# airball_sensor_board_v6.net
KiCad netlist of a schematic drawn in EAGLE
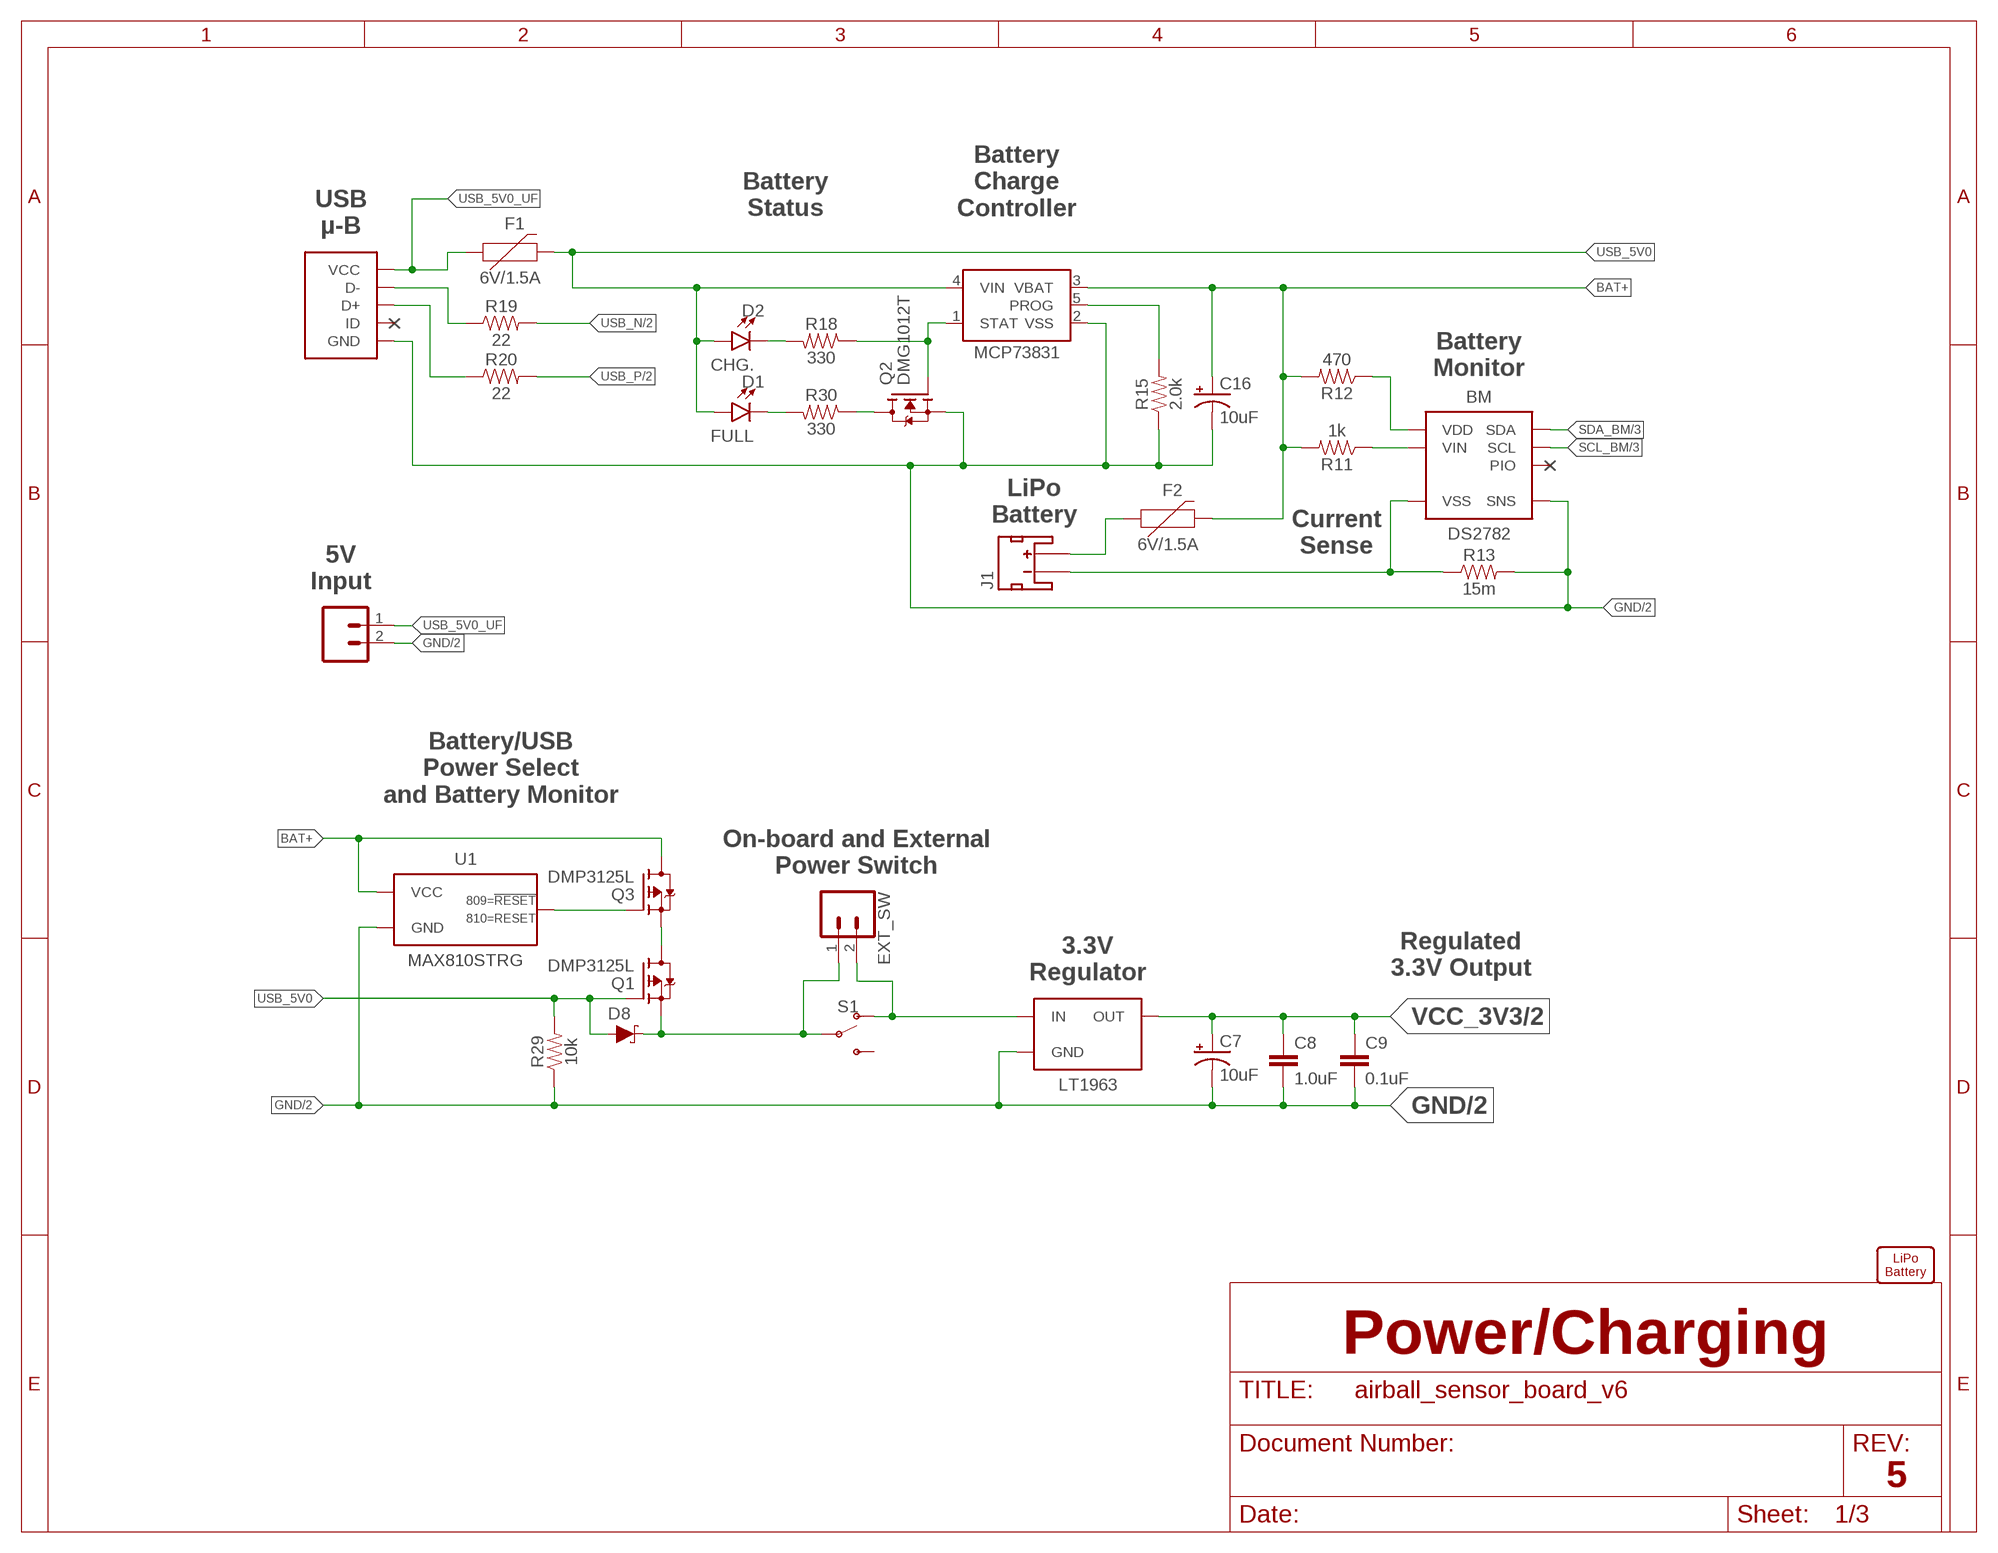
[diagram p0: schematic, sheet 1]
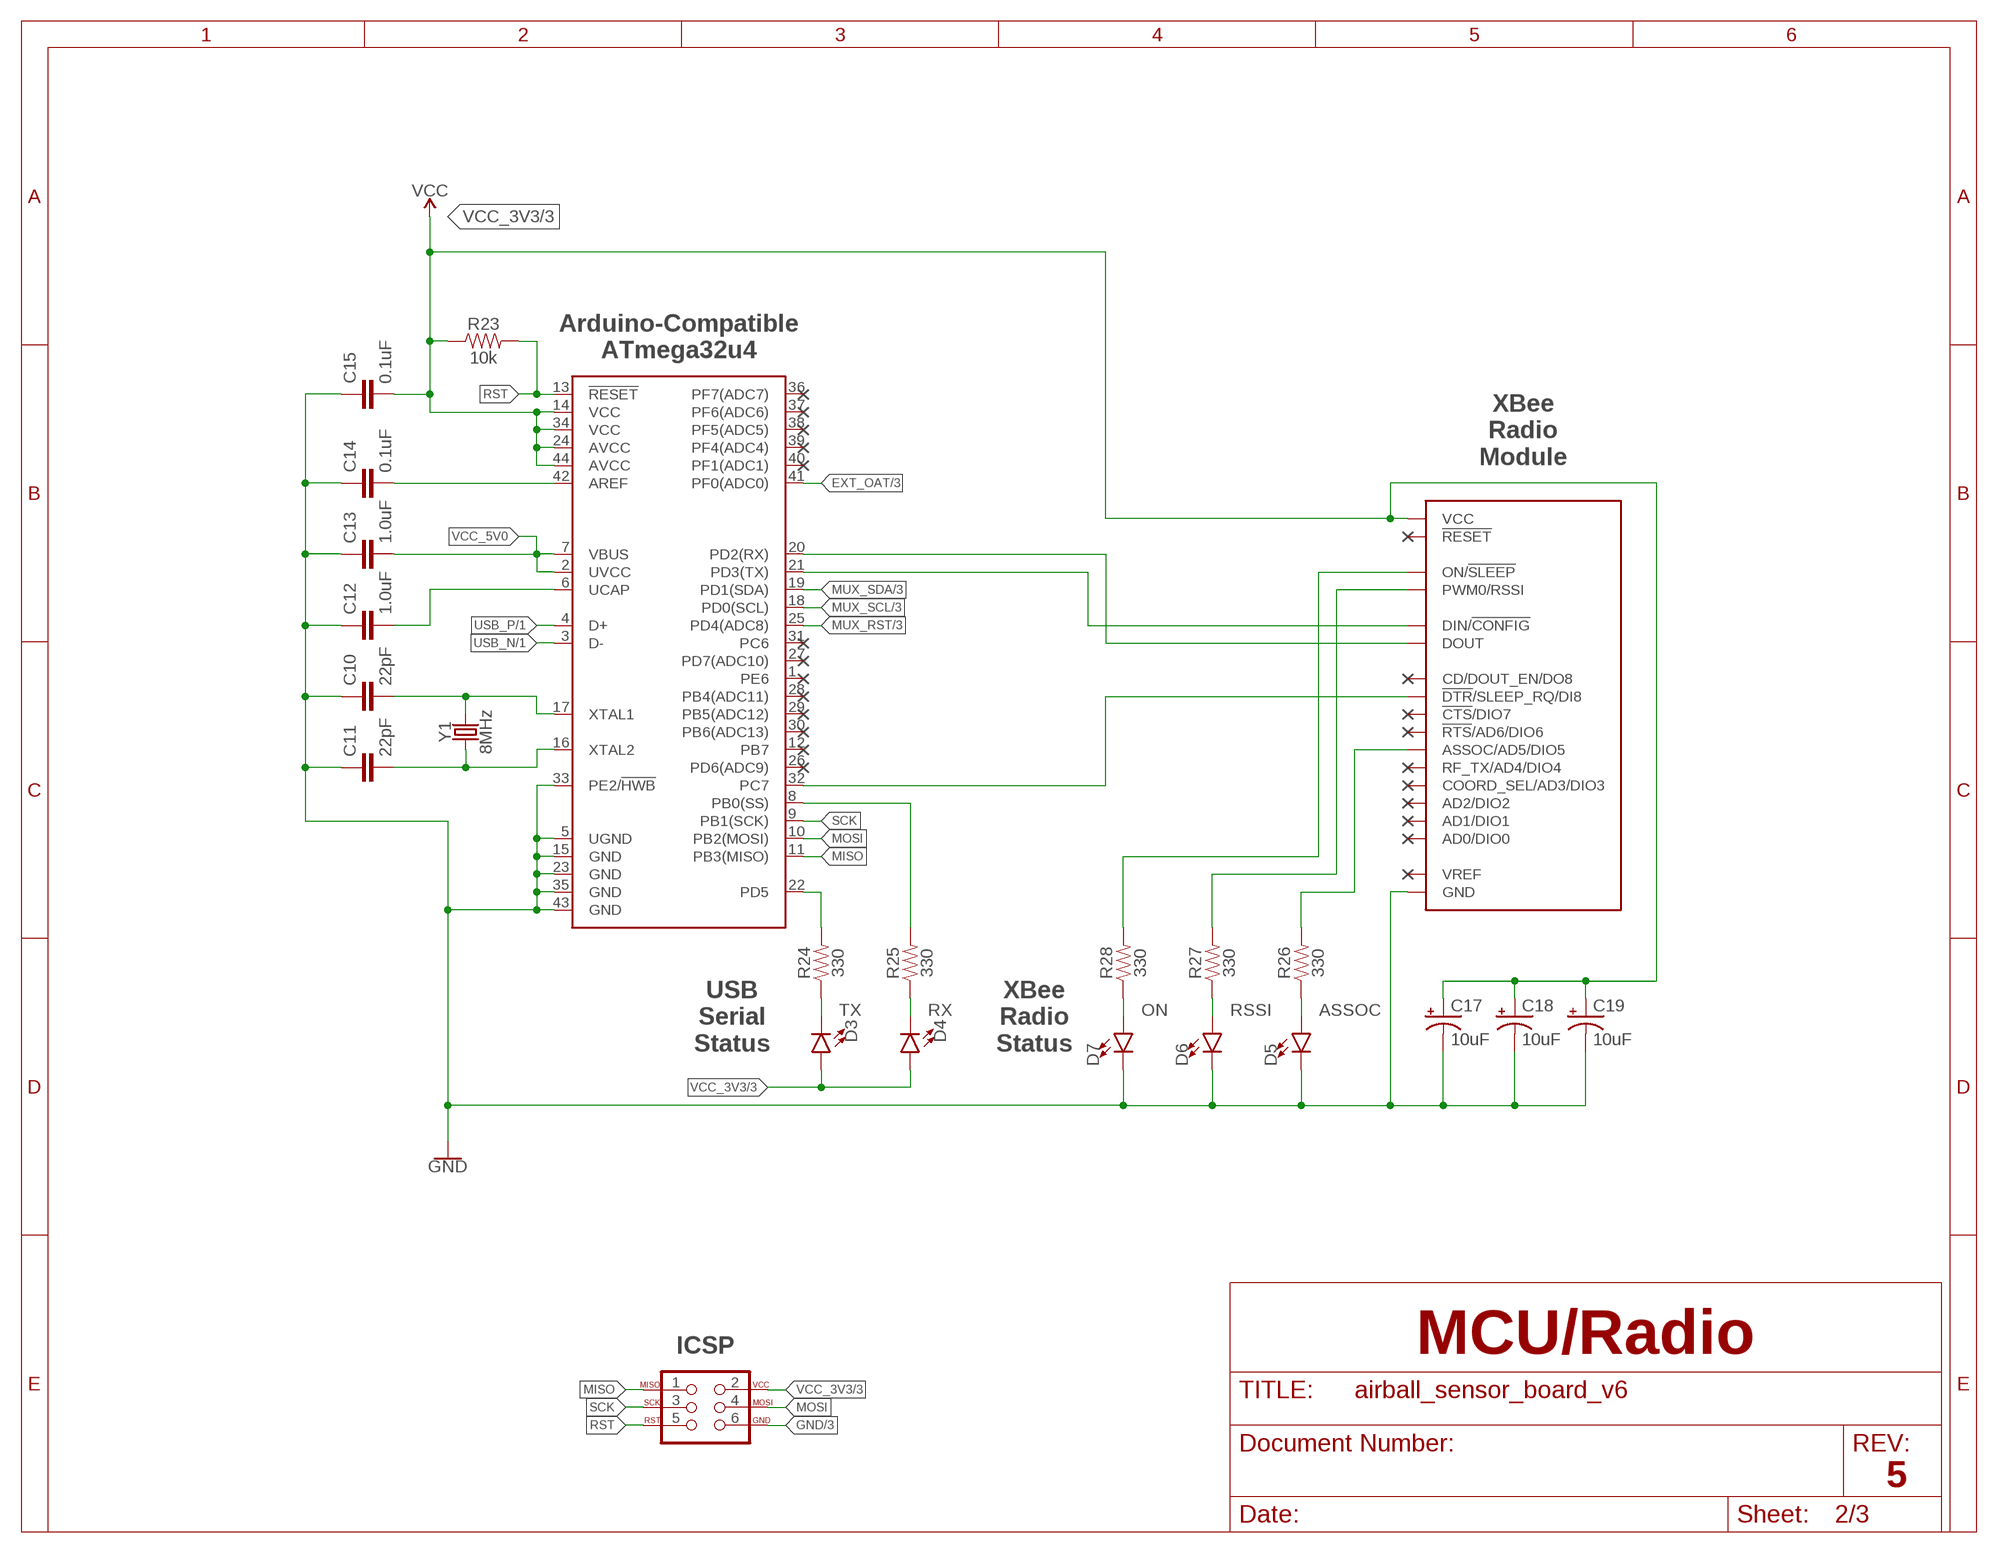
[diagram p1: schematic, sheet 2]
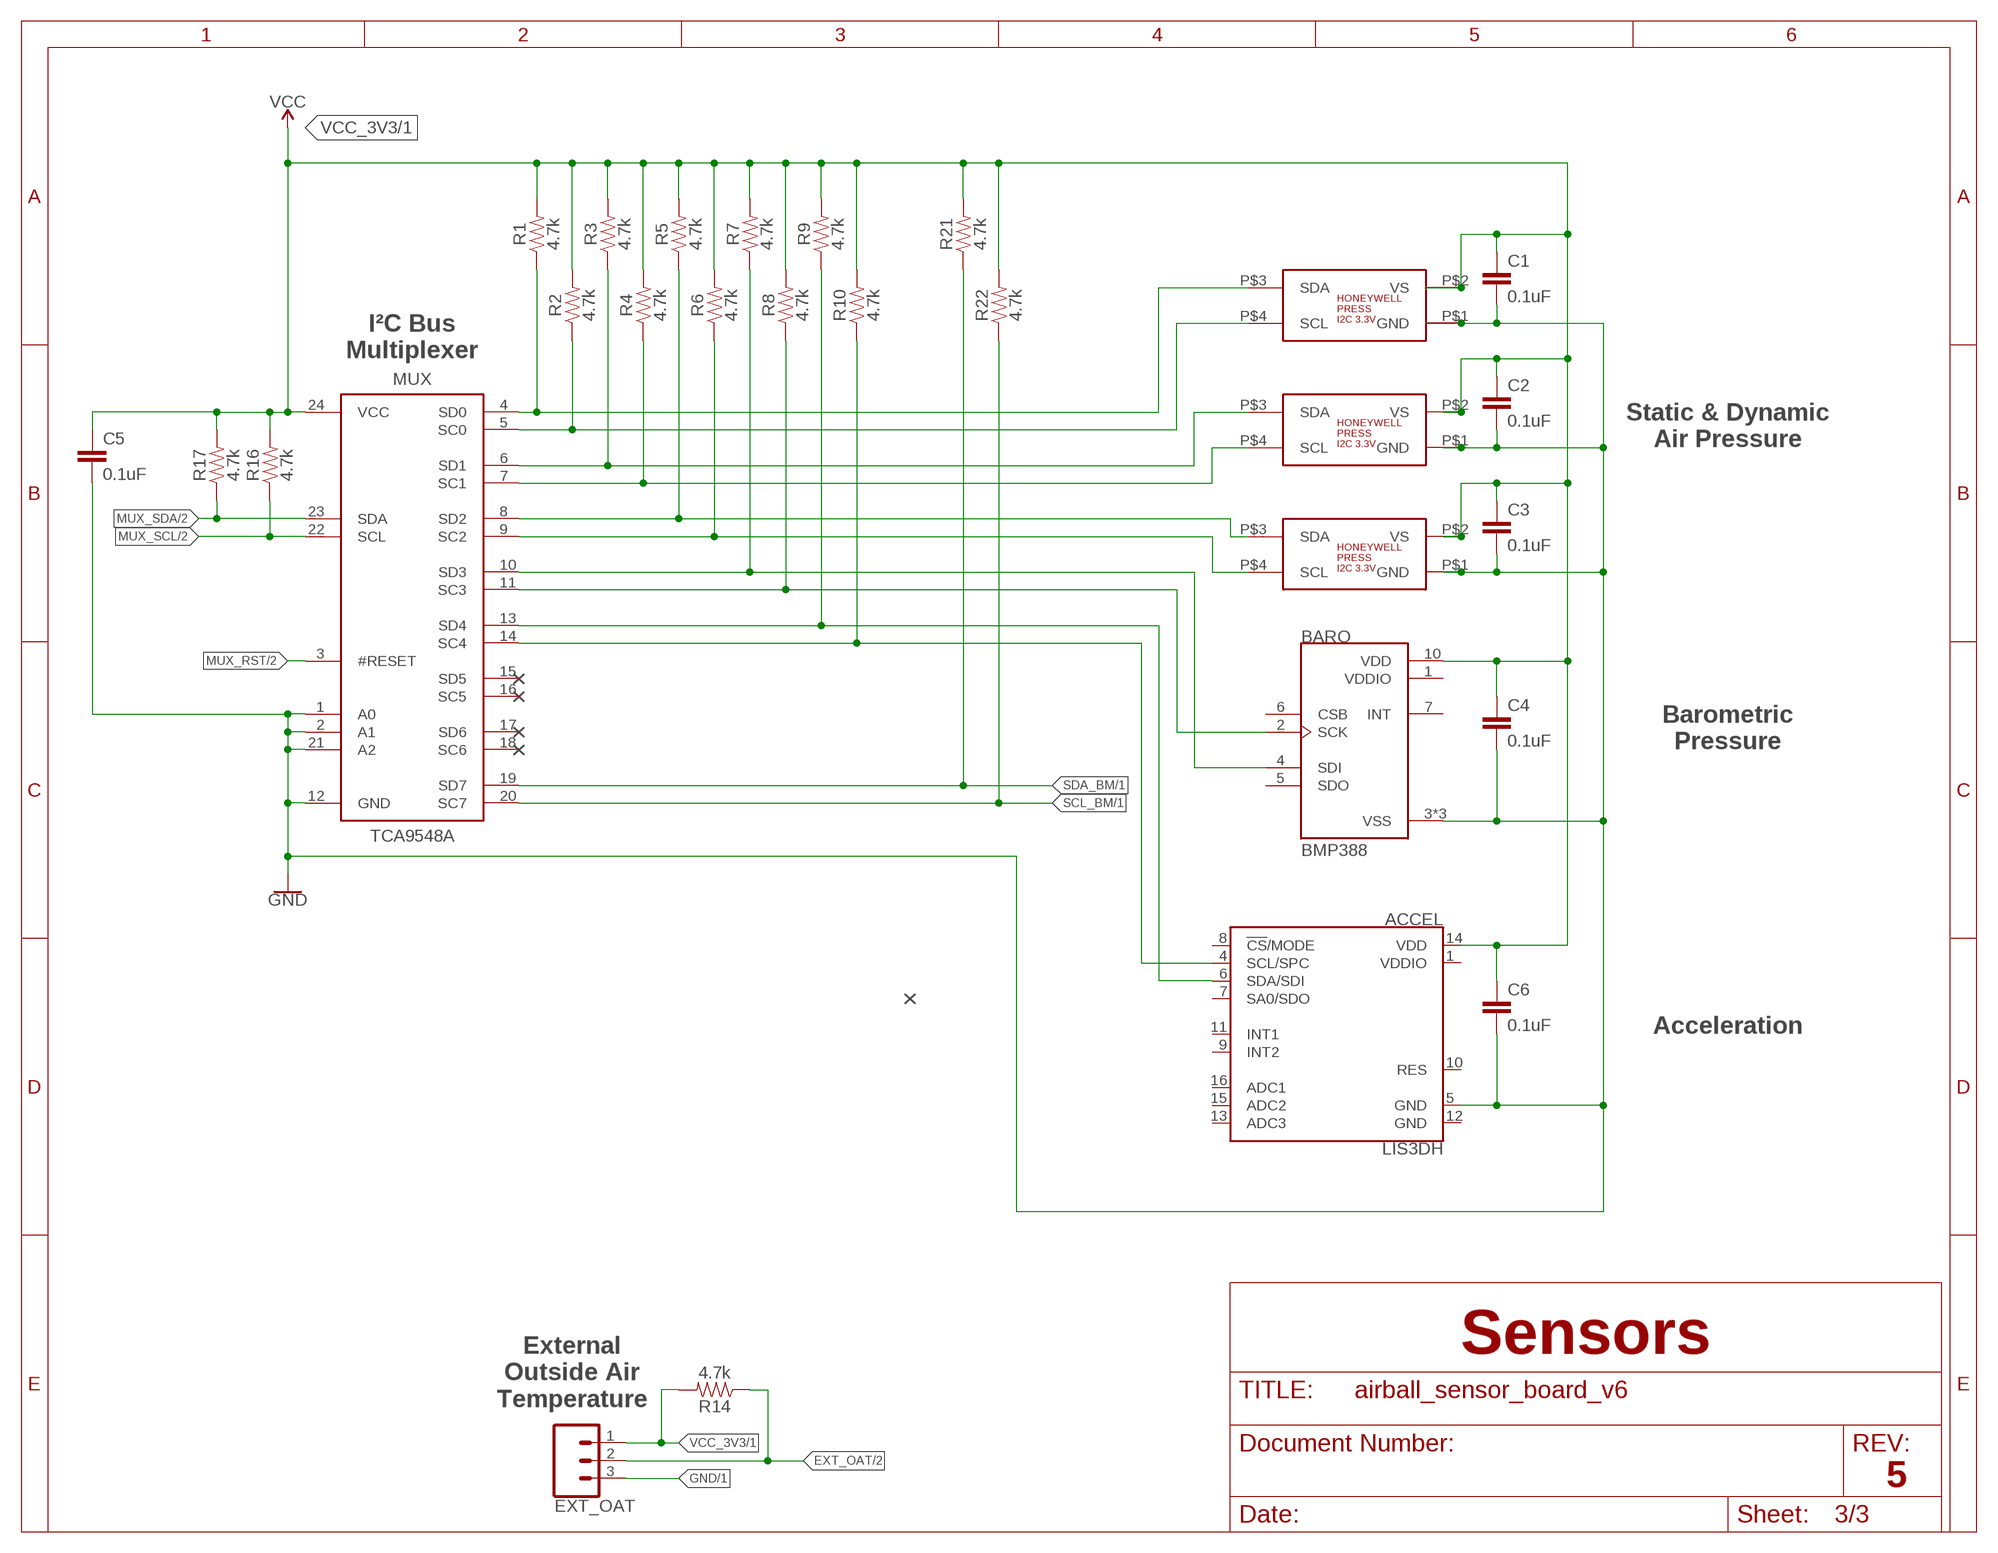
[diagram p2: schematic, sheet 3]

(export (version "E")
  (design (tool "Eeschema 10.0.6"))
  (components
    (comp (ref "C10")
      (value "22pF")
      (footprint "eagle-import:0603")
      (libsource (lib "eagle-import") (part "22PF-0603-50V-5%"))
    )
    (comp (ref "C11")
      (value "22pF")
      (footprint "eagle-import:0603")
      (libsource (lib "eagle-import") (part "22PF-0603-50V-5%"))
    )
    (comp (ref "C12")
      (value "1.0uF")
      (footprint "eagle-import:0603")
      (libsource (lib "eagle-import") (part "1.0UF-0603-16V-10%"))
    )
    (comp (ref "C13")
      (value "1.0uF")
      (footprint "eagle-import:0603")
      (libsource (lib "eagle-import") (part "1.0UF-0603-16V-10%"))
    )
    (comp (ref "C14")
      (value "0.1uF")
      (footprint "eagle-import:0603")
      (libsource (lib "eagle-import") (part "0.1UF-0603-25V-5%"))
    )
    (comp (ref "C15")
      (value "0.1uF")
      (footprint "eagle-import:0603")
      (libsource (lib "eagle-import") (part "0.1UF-0603-25V-5%"))
    )
    (comp (ref "C17")
      (value "10uF")
      (footprint "eagle-import:EIA3216")
      (libsource (lib "eagle-import") (part "10UF-POLAR-EIA3216-16V-10%(TANT)"))
    )
    (comp (ref "C18")
      (value "10uF")
      (footprint "eagle-import:EIA3216")
      (libsource (lib "eagle-import") (part "10UF-POLAR-EIA3216-16V-10%(TANT)"))
    )
    (comp (ref "C19")
      (value "10uF")
      (footprint "eagle-import:EIA3216")
      (libsource (lib "eagle-import") (part "10UF-POLAR-EIA3216-16V-10%(TANT)"))
    )
    (comp (ref "D3")
      (value "LED0603")
      (footprint "eagle-import:LED-0603")
      (libsource (lib "eagle-import") (part "LED0603"))
    )
    (comp (ref "D4")
      (value "LED0603")
      (footprint "eagle-import:LED-0603")
      (libsource (lib "eagle-import") (part "LED0603"))
    )
    (comp (ref "D5")
      (value "LED0603")
      (footprint "eagle-import:LED-0603")
      (libsource (lib "eagle-import") (part "LED0603"))
    )
    (comp (ref "D6")
      (value "LED0603")
      (footprint "eagle-import:LED-0603")
      (libsource (lib "eagle-import") (part "LED0603"))
    )
    (comp (ref "D7")
      (value "LED0603")
      (footprint "eagle-import:LED-0603")
      (libsource (lib "eagle-import") (part "LED0603"))
    )
    (comp (ref "ICSP")
      (value "AVR_SPI_PROG_3X2PTH")
      (footprint "eagle-import:2X3")
      (libsource (lib "eagle-import") (part "AVR_SPI_PROG_3X2PTH"))
    )
    (comp (ref "MCU")
      (value "32U4")
      (footprint "eagle-import:TQFP44")
      (libsource (lib "eagle-import") (part "ATMEGA32U4TQFP-44"))
    )
    (comp (ref "R23")
      (value "10k")
      (footprint "eagle-import:0603")
      (libsource (lib "eagle-import") (part "10KOHM-0603-1/10W-1%"))
    )
    (comp (ref "R24")
      (value "330")
      (footprint "eagle-import:0603")
      (libsource (lib "eagle-import") (part "330OHM-0603-1/10W-1%"))
    )
    (comp (ref "R25")
      (value "330")
      (footprint "eagle-import:0603")
      (libsource (lib "eagle-import") (part "330OHM-0603-1/10W-1%"))
    )
    (comp (ref "R26")
      (value "330")
      (footprint "eagle-import:0603")
      (libsource (lib "eagle-import") (part "330OHM-0603-1/10W-1%"))
    )
    (comp (ref "R27")
      (value "330")
      (footprint "eagle-import:0603")
      (libsource (lib "eagle-import") (part "330OHM-0603-1/10W-1%"))
    )
    (comp (ref "R28")
      (value "330")
      (footprint "eagle-import:0603")
      (libsource (lib "eagle-import") (part "330OHM-0603-1/10W-1%"))
    )
    (comp (ref "XBEE")
      (value "XBEE-PRO-SMD")
      (footprint "eagle-import:XBEE-PRO-SMD")
      (libsource (lib "eagle-import") (part "XBEE-PRO-SMD"))
    )
    (comp (ref "Y1")
      (value "8MHz")
      (footprint "eagle-import:CRYSTAL-SMD-5X3.2-4PAD")
      (libsource (lib "eagle-import") (part "CRYSTAL-8MHZSMD-5X3.2"))
    )
    (comp (ref "BM")
      (value "DS2782")
      (footprint "eagle-import:TSSOP8")
      (libsource (lib "eagle-import") (part "DS2782"))
    )
    (comp (ref "C7")
      (value "10uF")
      (footprint "eagle-import:EIA3216")
      (libsource (lib "eagle-import") (part "10UF-POLAR-EIA3216-16V-10%(TANT)"))
    )
    (comp (ref "C8")
      (value "1.0uF")
      (footprint "eagle-import:0603")
      (libsource (lib "eagle-import") (part "1.0UF-0603-16V-10%"))
    )
    (comp (ref "C9")
      (value "0.1uF")
      (footprint "eagle-import:0603")
      (libsource (lib "eagle-import") (part "0.1UF-0603-25V-5%"))
    )
    (comp (ref "C16")
      (value "10uF")
      (footprint "eagle-import:EIA3216")
      (libsource (lib "eagle-import") (part "10UF-POLAR-EIA3216-16V-10%(TANT)"))
    )
    (comp (ref "CC")
      (value "MCP73831")
      (footprint "eagle-import:SOT23-5")
      (libsource (lib "eagle-import") (part "MCP73831"))
    )
    (comp (ref "D1")
      (value "LED0603")
      (footprint "eagle-import:LED-0603")
      (libsource (lib "eagle-import") (part "LED0603"))
    )
    (comp (ref "D2")
      (value "LED0603")
      (footprint "eagle-import:LED-0603")
      (libsource (lib "eagle-import") (part "LED0603"))
    )
    (comp (ref "D8")
      (value "DIODE-SCHOTTKY-BAT20J")
      (footprint "eagle-import:SOD-323")
      (libsource (lib "eagle-import") (part "DIODE-SCHOTTKY-BAT20J"))
    )
    (comp (ref "EXT_POWER")
      (value "CONN_02")
      (footprint "eagle-import:1X02")
      (libsource (lib "eagle-import") (part "CONN_02"))
    )
    (comp (ref "EXT_SW")
      (value "CONN_02")
      (footprint "eagle-import:1X02")
      (libsource (lib "eagle-import") (part "CONN_02"))
    )
    (comp (ref "F1")
      (value "6V/1.5A")
      (footprint "eagle-import:1206")
      (libsource (lib "eagle-import") (part "PPTC_HALF-AMP"))
    )
    (comp (ref "F2")
      (value "6V/1.5A")
      (footprint "eagle-import:1206")
      (libsource (lib "eagle-import") (part "PPTC_HALF-AMP"))
    )
    (comp (ref "J1")
      (value "JST_2MM_MALE")
      (footprint "eagle-import:JST-2-SMD")
      (libsource (lib "eagle-import") (part "JST_2MM_MALE"))
    )
    (comp (ref "JP1")
      (value "USB_MICROB_PLUG")
      (footprint "eagle-import:USB_MICRO_B_TYCO")
      (libsource (lib "eagle-import") (part "USB_MICROB_PLUG"))
    )
    (comp (ref "Q1")
      (value "DMP3125L")
      (footprint "eagle-import:SOT23-3")
      (libsource (lib "eagle-import") (part "DMP3125L"))
    )
    (comp (ref "Q2")
      (value "DMG1012T")
      (footprint "eagle-import:SOT523-3")
      (libsource (lib "eagle-import") (part "DMG1012T"))
    )
    (comp (ref "Q3")
      (value "DMP3125L")
      (footprint "eagle-import:SOT23-3")
      (libsource (lib "eagle-import") (part "DMP3125L"))
    )
    (comp (ref "R11")
      (value "1k")
      (footprint "eagle-import:0603")
      (libsource (lib "eagle-import") (part "1KOHM-0603-1/10W-1%"))
    )
    (comp (ref "R12")
      (value "470")
      (footprint "eagle-import:0603")
      (libsource (lib "eagle-import") (part "470OHM-0603-1/10W-1%"))
    )
    (comp (ref "R13")
      (value "15m")
      (footprint "eagle-import:1206")
      (libsource (lib "eagle-import") (part "RESISTOR1206"))
    )
    (comp (ref "R15")
      (value "2.0k")
      (footprint "eagle-import:0603")
      (libsource (lib "eagle-import") (part "2.0KOHM-0603-1/10W-5%"))
    )
    (comp (ref "R18")
      (value "330")
      (footprint "eagle-import:0603")
      (libsource (lib "eagle-import") (part "330OHM-0603-1/10W-1%"))
    )
    (comp (ref "R19")
      (value "22")
      (footprint "eagle-import:0603")
      (libsource (lib "eagle-import") (part "22OHM-0603-1/10W-1%"))
    )
    (comp (ref "R20")
      (value "22")
      (footprint "eagle-import:0603")
      (libsource (lib "eagle-import") (part "22OHM-0603-1/10W-1%"))
    )
    (comp (ref "R29")
      (value "10k")
      (footprint "eagle-import:0603")
      (libsource (lib "eagle-import") (part "10KOHM-0603-1/10W-1%"))
    )
    (comp (ref "R30")
      (value "330")
      (footprint "eagle-import:0603")
      (libsource (lib "eagle-import") (part "330OHM-0603-1/10W-1%"))
    )
    (comp (ref "S1")
      (value "SWITCH-SPDT-SMD-RIGHT-ANGLE")
      (footprint "eagle-import:SWITCH_SPST_SMD_A")
      (libsource (lib "eagle-import") (part "SWITCH-SPDT-SMD-RIGHT-ANGLE"))
    )
    (comp (ref "U$3")
      (value "LIPO_BATTERY_OUTLINE-1000MAH")
      (footprint "eagle-import:SPARKFUN_LIPO_1000MAH")
      (libsource (lib "eagle-import") (part "LIPO_BATTERY_OUTLINE-1000MAH"))
    )
    (comp (ref "U1")
      (value "MAX810STRG")
      (footprint "eagle-import:SOT23-3")
      (libsource (lib "eagle-import") (part "MAX809/810"))
    )
    (comp (ref "VREG")
      (value "LT1963")
      (footprint "eagle-import:SOT223-3")
      (libsource (lib "eagle-import") (part "LT1963"))
    )
    (comp (ref "ACCEL")
      (value "LIS3DH")
      (footprint "eagle-import:LGA-16-3X3")
      (libsource (lib "eagle-import") (part "LIS3DH"))
    )
    (comp (ref "BARO")
      (value "BMP388")
      (footprint "eagle-import:PQFN50P200X200X80-10N")
      (fields (field (name "MF") "Bosch Sensortec"))
      (libsource (lib "eagle-import") (part "BMP388"))
    )
    (comp (ref "C1")
      (value "0.1uF")
      (footprint "eagle-import:0603")
      (libsource (lib "eagle-import") (part "0.1UF-0603-25V-5%"))
    )
    (comp (ref "C2")
      (value "0.1uF")
      (footprint "eagle-import:0603")
      (libsource (lib "eagle-import") (part "0.1UF-0603-25V-5%"))
    )
    (comp (ref "C3")
      (value "0.1uF")
      (footprint "eagle-import:0603")
      (libsource (lib "eagle-import") (part "0.1UF-0603-25V-5%"))
    )
    (comp (ref "C4")
      (value "0.1uF")
      (footprint "eagle-import:0603")
      (libsource (lib "eagle-import") (part "0.1UF-0603-25V-5%"))
    )
    (comp (ref "C5")
      (value "0.1uF")
      (footprint "eagle-import:0603")
      (libsource (lib "eagle-import") (part "0.1UF-0603-25V-5%"))
    )
    (comp (ref "C6")
      (value "0.1uF")
      (footprint "eagle-import:0603")
      (libsource (lib "eagle-import") (part "0.1UF-0603-25V-5%"))
    )
    (comp (ref "DP0")
      (value "HONEYWELL_TRUSTABILITY_I2C_3.3V")
      (footprint "eagle-import:HONEYWELL_TRUSTABILITY_DIP_RR")
      (libsource (lib "eagle-import") (part "HONEYWELL_TRUSTABILITY_I2C_3.3V"))
    )
    (comp (ref "DPA")
      (value "HONEYWELL_TRUSTABILITY_I2C_3.3V")
      (footprint "eagle-import:HONEYWELL_TRUSTABILITY_DIP_RR")
      (libsource (lib "eagle-import") (part "HONEYWELL_TRUSTABILITY_I2C_3.3V"))
    )
    (comp (ref "DPB")
      (value "HONEYWELL_TRUSTABILITY_I2C_3.3V")
      (footprint "eagle-import:HONEYWELL_TRUSTABILITY_DIP_RR")
      (libsource (lib "eagle-import") (part "HONEYWELL_TRUSTABILITY_I2C_3.3V"))
    )
    (comp (ref "EXT_OAT")
      (value "CONN_03")
      (footprint "eagle-import:1X03")
      (libsource (lib "eagle-import") (part "CONN_03"))
    )
    (comp (ref "MUX")
      (value "TCA9548A")
      (footprint "eagle-import:TSSOP24")
      (libsource (lib "eagle-import") (part "TCA9548ATSSOP24"))
    )
    (comp (ref "R1")
      (value "4.7k")
      (footprint "eagle-import:0603")
      (libsource (lib "eagle-import") (part "4.7KOHM-0603-1/10W-1%"))
    )
    (comp (ref "R2")
      (value "4.7k")
      (footprint "eagle-import:0603")
      (libsource (lib "eagle-import") (part "4.7KOHM-0603-1/10W-1%"))
    )
    (comp (ref "R3")
      (value "4.7k")
      (footprint "eagle-import:0603")
      (libsource (lib "eagle-import") (part "4.7KOHM-0603-1/10W-1%"))
    )
    (comp (ref "R4")
      (value "4.7k")
      (footprint "eagle-import:0603")
      (libsource (lib "eagle-import") (part "4.7KOHM-0603-1/10W-1%"))
    )
    (comp (ref "R5")
      (value "4.7k")
      (footprint "eagle-import:0603")
      (libsource (lib "eagle-import") (part "4.7KOHM-0603-1/10W-1%"))
    )
    (comp (ref "R6")
      (value "4.7k")
      (footprint "eagle-import:0603")
      (libsource (lib "eagle-import") (part "4.7KOHM-0603-1/10W-1%"))
    )
    (comp (ref "R7")
      (value "4.7k")
      (footprint "eagle-import:0603")
      (libsource (lib "eagle-import") (part "4.7KOHM-0603-1/10W-1%"))
    )
    (comp (ref "R8")
      (value "4.7k")
      (footprint "eagle-import:0603")
      (libsource (lib "eagle-import") (part "4.7KOHM-0603-1/10W-1%"))
    )
    (comp (ref "R9")
      (value "4.7k")
      (footprint "eagle-import:0603")
      (libsource (lib "eagle-import") (part "4.7KOHM-0603-1/10W-1%"))
    )
    (comp (ref "R10")
      (value "4.7k")
      (footprint "eagle-import:0603")
      (libsource (lib "eagle-import") (part "4.7KOHM-0603-1/10W-1%"))
    )
    (comp (ref "R14")
      (value "4.7k")
      (footprint "eagle-import:0603")
      (libsource (lib "eagle-import") (part "4.7KOHM-0603-1/10W-1%"))
    )
    (comp (ref "R16")
      (value "4.7k")
      (footprint "eagle-import:0603")
      (libsource (lib "eagle-import") (part "4.7KOHM-0603-1/10W-1%"))
    )
    (comp (ref "R17")
      (value "4.7k")
      (footprint "eagle-import:0603")
      (libsource (lib "eagle-import") (part "4.7KOHM-0603-1/10W-1%"))
    )
    (comp (ref "R21")
      (value "4.7k")
      (footprint "eagle-import:0603")
      (libsource (lib "eagle-import") (part "4.7KOHM-0603-1/10W-1%"))
    )
    (comp (ref "R22")
      (value "4.7k")
      (footprint "eagle-import:0603")
      (libsource (lib "eagle-import") (part "4.7KOHM-0603-1/10W-1%"))
    )
  )
  (nets
    (net (code "1") (name "BAT+") (class "Default")
      (node (ref "C16") (pin "+") (pinfunction "+_+") (pintype "passive"))
      (node (ref "CC") (pin "3") (pinfunction "VBAT_3") (pintype "power_in"))
      (node (ref "F2") (pin "2") (pinfunction "2_2") (pintype "bidirectional"))
      (node (ref "Q3") (pin "3") (pinfunction "D_3") (pintype "passive"))
      (node (ref "R11") (pin "2") (pinfunction "2_2") (pintype "passive"))
      (node (ref "R12") (pin "2") (pinfunction "2_2") (pintype "passive"))
      (node (ref "U1") (pin "3") (pinfunction "VCC_3") (pintype "bidirectional"))
    )
    (net (code "2") (name "EXT_OAT") (class "Default")
      (node (ref "EXT_OAT") (pin "2") (pinfunction "2_2") (pintype "passive"))
      (node (ref "MCU") (pin "41") (pinfunction "PF0(ADC0)_41") (pintype "bidirectional"))
      (node (ref "R14") (pin "1") (pinfunction "1_1") (pintype "passive"))
    )
    (net (code "3") (name "GND") (class "Default")
      (node (ref "ACCEL") (pin "5") (pinfunction "GND_5") (pintype "bidirectional"))
      (node (ref "BARO") (pin "3") (pinfunction "VSS_3") (pintype "power_in"))
      (node (ref "BARO") (pin "8") (pinfunction "VSS_8") (pintype "power_in"))
      (node (ref "BARO") (pin "9") (pinfunction "VSS_9") (pintype "power_in"))
      (node (ref "BM") (pin "7") (pinfunction "SNS_7") (pintype "power_in"))
      (node (ref "C1") (pin "2") (pinfunction "2_2") (pintype "passive"))
      (node (ref "C10") (pin "1") (pinfunction "1_1") (pintype "passive"))
      (node (ref "C11") (pin "1") (pinfunction "1_1") (pintype "passive"))
      (node (ref "C12") (pin "1") (pinfunction "1_1") (pintype "passive"))
      (node (ref "C13") (pin "1") (pinfunction "1_1") (pintype "passive"))
      (node (ref "C14") (pin "1") (pinfunction "1_1") (pintype "passive"))
      (node (ref "C15") (pin "1") (pinfunction "1_1") (pintype "passive"))
      (node (ref "C16") (pin "-") (pinfunction "-_-") (pintype "passive"))
      (node (ref "C17") (pin "-") (pinfunction "-_-") (pintype "passive"))
      (node (ref "C18") (pin "-") (pinfunction "-_-") (pintype "passive"))
      (node (ref "C19") (pin "-") (pinfunction "-_-") (pintype "passive"))
      (node (ref "C2") (pin "2") (pinfunction "2_2") (pintype "passive"))
      (node (ref "C3") (pin "2") (pinfunction "2_2") (pintype "passive"))
      (node (ref "C4") (pin "2") (pinfunction "2_2") (pintype "passive"))
      (node (ref "C5") (pin "2") (pinfunction "2_2") (pintype "passive"))
      (node (ref "C6") (pin "2") (pinfunction "2_2") (pintype "passive"))
      (node (ref "C7") (pin "-") (pinfunction "-_-") (pintype "passive"))
      (node (ref "C8") (pin "2") (pinfunction "2_2") (pintype "passive"))
      (node (ref "C9") (pin "2") (pinfunction "2_2") (pintype "passive"))
      (node (ref "CC") (pin "2") (pinfunction "VSS_2") (pintype "power_in"))
      (node (ref "D5") (pin "C") (pinfunction "C_C") (pintype "passive"))
      (node (ref "D6") (pin "C") (pinfunction "C_C") (pintype "passive"))
      (node (ref "D7") (pin "C") (pinfunction "C_C") (pintype "passive"))
      (node (ref "DP0") (pin "P$1") (pinfunction "GND_P$1") (pintype "bidirectional"))
      (node (ref "DPA") (pin "P$1") (pinfunction "GND_P$1") (pintype "bidirectional"))
      (node (ref "DPB") (pin "P$1") (pinfunction "GND_P$1") (pintype "bidirectional"))
      (node (ref "EXT_OAT") (pin "3") (pinfunction "3_3") (pintype "passive"))
      (node (ref "EXT_POWER") (pin "2") (pinfunction "2_2") (pintype "passive"))
      (node (ref "ICSP") (pin "6") (pinfunction "6_6") (pintype "passive"))
      (node (ref "JP1") (pin "5") (pinfunction "GND_5") (pintype "power_in"))
      (node (ref "JP1") (pin "SH@1") (pinfunction "GND_SH@1") (pintype "power_in"))
      (node (ref "JP1") (pin "SH@2") (pinfunction "GND_SH@2") (pintype "power_in"))
      (node (ref "JP1") (pin "SH@3") (pinfunction "GND_SH@3") (pintype "power_in"))
      (node (ref "JP1") (pin "SH@4") (pinfunction "GND_SH@4") (pintype "power_in"))
      (node (ref "MCU") (pin "15") (pinfunction "GND_15") (pintype "bidirectional"))
      (node (ref "MCU") (pin "23") (pinfunction "GND_23") (pintype "bidirectional"))
      (node (ref "MCU") (pin "33") (pinfunction "PE2/~{HWB}_33") (pintype "bidirectional"))
      (node (ref "MCU") (pin "35") (pinfunction "GND_35") (pintype "bidirectional"))
      (node (ref "MCU") (pin "43") (pinfunction "GND_43") (pintype "bidirectional"))
      (node (ref "MCU") (pin "5") (pinfunction "UGND_5") (pintype "bidirectional"))
      (node (ref "MUX") (pin "1") (pinfunction "A0_1") (pintype "bidirectional"))
      (node (ref "MUX") (pin "12") (pinfunction "GND_12") (pintype "bidirectional"))
      (node (ref "MUX") (pin "2") (pinfunction "A1_2") (pintype "bidirectional"))
      (node (ref "MUX") (pin "21") (pinfunction "A2_21") (pintype "bidirectional"))
      (node (ref "Q2") (pin "3") (pinfunction "S_3") (pintype "passive"))
      (node (ref "R13") (pin "2") (pinfunction "2_2") (pintype "passive"))
      (node (ref "R15") (pin "1") (pinfunction "1_1") (pintype "passive"))
      (node (ref "R29") (pin "1") (pinfunction "1_1") (pintype "passive"))
      (node (ref "U1") (pin "1") (pinfunction "GND_1") (pintype "bidirectional"))
      (node (ref "VREG") (pin "2") (pinfunction "GND_2") (pintype "power_in"))
      (node (ref "VREG") (pin "TAB") (pinfunction "GND_TAB") (pintype "power_in"))
      (node (ref "XBEE") (pin "10") (pinfunction "GND_10") (pintype "power_in"))
    )
    (net (code "4") (name "MISO") (class "Default")
      (node (ref "ICSP") (pin "1") (pinfunction "1_1") (pintype "passive"))
      (node (ref "MCU") (pin "11") (pinfunction "PB3(MISO)_11") (pintype "bidirectional"))
    )
    (net (code "5") (name "MOSI") (class "Default")
      (node (ref "ICSP") (pin "4") (pinfunction "4_4") (pintype "passive"))
      (node (ref "MCU") (pin "10") (pinfunction "PB2(MOSI)_10") (pintype "bidirectional"))
    )
    (net (code "6") (name "MUX_RST") (class "Default")
      (node (ref "MCU") (pin "25") (pinfunction "PD4(ADC8)_25") (pintype "bidirectional"))
      (node (ref "MUX") (pin "3") (pinfunction "#RESET_3") (pintype "bidirectional"))
    )
    (net (code "7") (name "MUX_SCL") (class "Default")
      (node (ref "MCU") (pin "18") (pinfunction "PD0(SCL)_18") (pintype "bidirectional"))
      (node (ref "MUX") (pin "22") (pinfunction "SCL_22") (pintype "bidirectional"))
      (node (ref "R16") (pin "1") (pinfunction "1_1") (pintype "passive"))
    )
    (net (code "8") (name "MUX_SDA") (class "Default")
      (node (ref "MCU") (pin "19") (pinfunction "PD1(SDA)_19") (pintype "bidirectional"))
      (node (ref "MUX") (pin "23") (pinfunction "SDA_23") (pintype "bidirectional"))
      (node (ref "R17") (pin "1") (pinfunction "1_1") (pintype "passive"))
    )
    (net (code "9") (name "Net-(ACCEL-SCL{slash}SPC)") (class "Default")
      (node (ref "ACCEL") (pin "4") (pinfunction "SCL/SPC_4") (pintype "bidirectional"))
      (node (ref "MUX") (pin "14") (pinfunction "SC4_14") (pintype "bidirectional"))
      (node (ref "R10") (pin "1") (pinfunction "1_1") (pintype "passive"))
    )
    (net (code "10") (name "Net-(ACCEL-SDA{slash}SDI)") (class "Default")
      (node (ref "ACCEL") (pin "6") (pinfunction "SDA/SDI_6") (pintype "bidirectional"))
      (node (ref "MUX") (pin "13") (pinfunction "SD4_13") (pintype "bidirectional"))
      (node (ref "R9") (pin "1") (pinfunction "1_1") (pintype "passive"))
    )
    (net (code "11") (name "Net-(BARO-SCK)") (class "Default")
      (node (ref "BARO") (pin "2") (pinfunction "SCK_2") (pintype "input"))
      (node (ref "MUX") (pin "11") (pinfunction "SC3_11") (pintype "bidirectional"))
      (node (ref "R8") (pin "1") (pinfunction "1_1") (pintype "passive"))
    )
    (net (code "12") (name "Net-(BARO-SDI)") (class "Default")
      (node (ref "BARO") (pin "4") (pinfunction "SDI_4") (pintype "bidirectional"))
      (node (ref "MUX") (pin "10") (pinfunction "SD3_10") (pintype "bidirectional"))
      (node (ref "R7") (pin "1") (pinfunction "1_1") (pintype "passive"))
    )
    (net (code "13") (name "Net-(BM-VDD)") (class "Default")
      (node (ref "BM") (pin "4") (pinfunction "VDD_4") (pintype "power_in"))
      (node (ref "R12") (pin "1") (pinfunction "1_1") (pintype "passive"))
    )
    (net (code "14") (name "Net-(BM-VIN)") (class "Default")
      (node (ref "BM") (pin "3") (pinfunction "VIN_3") (pintype "power_in"))
      (node (ref "R11") (pin "1") (pinfunction "1_1") (pintype "passive"))
    )
    (net (code "15") (name "Net-(BM-VSS)") (class "Default")
      (node (ref "BM") (pin "2") (pinfunction "VSS_2") (pintype "power_in"))
      (node (ref "J1") (pin "1") (pinfunction "-_1") (pintype "bidirectional"))
      (node (ref "R13") (pin "1") (pinfunction "1_1") (pintype "passive"))
    )
    (net (code "16") (name "Net-(CC-PROG)") (class "Default")
      (node (ref "CC") (pin "5") (pinfunction "PROG_5") (pintype "input"))
      (node (ref "R15") (pin "2") (pinfunction "2_2") (pintype "passive"))
    )
    (net (code "17") (name "Net-(CC-STAT)") (class "Default")
      (node (ref "CC") (pin "1") (pinfunction "STAT_1") (pintype "output"))
      (node (ref "Q2") (pin "1") (pinfunction "G_1") (pintype "passive"))
      (node (ref "R18") (pin "1") (pinfunction "1_1") (pintype "passive"))
    )
    (net (code "18") (name "Net-(D1-PadC)") (class "Default")
      (node (ref "D1") (pin "C") (pinfunction "C_C") (pintype "passive"))
      (node (ref "R30") (pin "2") (pinfunction "2_2") (pintype "passive"))
    )
    (net (code "19") (name "Net-(D2-PadC)") (class "Default")
      (node (ref "D2") (pin "C") (pinfunction "C_C") (pintype "passive"))
      (node (ref "R18") (pin "2") (pinfunction "2_2") (pintype "passive"))
    )
    (net (code "20") (name "Net-(D3-PadC)") (class "Default")
      (node (ref "D3") (pin "C") (pinfunction "C_C") (pintype "passive"))
      (node (ref "R24") (pin "1") (pinfunction "1_1") (pintype "passive"))
    )
    (net (code "21") (name "Net-(D4-PadC)") (class "Default")
      (node (ref "D4") (pin "C") (pinfunction "C_C") (pintype "passive"))
      (node (ref "R25") (pin "1") (pinfunction "1_1") (pintype "passive"))
    )
    (net (code "22") (name "Net-(D5-PadA)") (class "Default")
      (node (ref "D5") (pin "A") (pinfunction "A_A") (pintype "passive"))
      (node (ref "R26") (pin "1") (pinfunction "1_1") (pintype "passive"))
    )
    (net (code "23") (name "Net-(D6-PadA)") (class "Default")
      (node (ref "D6") (pin "A") (pinfunction "A_A") (pintype "passive"))
      (node (ref "R27") (pin "1") (pinfunction "1_1") (pintype "passive"))
    )
    (net (code "24") (name "Net-(D7-PadA)") (class "Default")
      (node (ref "D7") (pin "A") (pinfunction "A_A") (pintype "passive"))
      (node (ref "R28") (pin "1") (pinfunction "1_1") (pintype "passive"))
    )
    (net (code "25") (name "Net-(DP0-SCL)") (class "Default")
      (node (ref "DP0") (pin "P$4") (pinfunction "SCL_P$4") (pintype "bidirectional"))
      (node (ref "MUX") (pin "5") (pinfunction "SC0_5") (pintype "bidirectional"))
      (node (ref "R2") (pin "1") (pinfunction "1_1") (pintype "passive"))
    )
    (net (code "26") (name "Net-(DP0-SDA)") (class "Default")
      (node (ref "DP0") (pin "P$3") (pinfunction "SDA_P$3") (pintype "bidirectional"))
      (node (ref "MUX") (pin "4") (pinfunction "SD0_4") (pintype "bidirectional"))
      (node (ref "R1") (pin "1") (pinfunction "1_1") (pintype "passive"))
    )
    (net (code "27") (name "Net-(DPA-SCL)") (class "Default")
      (node (ref "DPA") (pin "P$4") (pinfunction "SCL_P$4") (pintype "bidirectional"))
      (node (ref "MUX") (pin "7") (pinfunction "SC1_7") (pintype "bidirectional"))
      (node (ref "R4") (pin "1") (pinfunction "1_1") (pintype "passive"))
    )
    (net (code "28") (name "Net-(DPA-SDA)") (class "Default")
      (node (ref "DPA") (pin "P$3") (pinfunction "SDA_P$3") (pintype "bidirectional"))
      (node (ref "MUX") (pin "6") (pinfunction "SD1_6") (pintype "bidirectional"))
      (node (ref "R3") (pin "1") (pinfunction "1_1") (pintype "passive"))
    )
    (net (code "29") (name "Net-(DPB-SCL)") (class "Default")
      (node (ref "DPB") (pin "P$4") (pinfunction "SCL_P$4") (pintype "bidirectional"))
      (node (ref "MUX") (pin "9") (pinfunction "SC2_9") (pintype "bidirectional"))
      (node (ref "R6") (pin "1") (pinfunction "1_1") (pintype "passive"))
    )
    (net (code "30") (name "Net-(DPB-SDA)") (class "Default")
      (node (ref "DPB") (pin "P$3") (pinfunction "SDA_P$3") (pintype "bidirectional"))
      (node (ref "MUX") (pin "8") (pinfunction "SD2_8") (pintype "bidirectional"))
      (node (ref "R5") (pin "1") (pinfunction "1_1") (pintype "passive"))
    )
    (net (code "31") (name "Net-(J1-+)") (class "Default")
      (node (ref "F2") (pin "1") (pinfunction "1_1") (pintype "bidirectional"))
      (node (ref "J1") (pin "2") (pinfunction "+_2") (pintype "bidirectional"))
    )
    (net (code "32") (name "Net-(JP1-D+)") (class "Default")
      (node (ref "JP1") (pin "3") (pinfunction "D+_3") (pintype "bidirectional"))
      (node (ref "R20") (pin "1") (pinfunction "1_1") (pintype "passive"))
    )
    (net (code "33") (name "Net-(JP1-D-)") (class "Default")
      (node (ref "JP1") (pin "2") (pinfunction "D-_2") (pintype "bidirectional"))
      (node (ref "R19") (pin "1") (pinfunction "1_1") (pintype "passive"))
    )
    (net (code "34") (name "Net-(MCU-AREF)") (class "Default")
      (node (ref "C14") (pin "2") (pinfunction "2_2") (pintype "passive"))
      (node (ref "MCU") (pin "42") (pinfunction "AREF_42") (pintype "bidirectional"))
    )
    (net (code "35") (name "Net-(MCU-PB0(SS))") (class "Default")
      (node (ref "MCU") (pin "8") (pinfunction "PB0(SS)_8") (pintype "bidirectional"))
      (node (ref "R25") (pin "2") (pinfunction "2_2") (pintype "passive"))
    )
    (net (code "36") (name "Net-(MCU-PC7)") (class "Default")
      (node (ref "MCU") (pin "32") (pinfunction "PC7_32") (pintype "bidirectional"))
      (node (ref "XBEE") (pin "9") (pinfunction "~{DTR}/SLEEP_RQ/DI8_9") (pintype "bidirectional"))
    )
    (net (code "37") (name "Net-(MCU-PD2(RX))") (class "Default")
      (node (ref "MCU") (pin "20") (pinfunction "PD2(RX)_20") (pintype "bidirectional"))
      (node (ref "XBEE") (pin "2") (pinfunction "DOUT_2") (pintype "output"))
    )
    (net (code "38") (name "Net-(MCU-PD3(TX))") (class "Default")
      (node (ref "MCU") (pin "21") (pinfunction "PD3(TX)_21") (pintype "bidirectional"))
      (node (ref "XBEE") (pin "3") (pinfunction "DIN/~{CONFIG}_3") (pintype "input"))
    )
    (net (code "39") (name "Net-(MCU-PD5)") (class "Default")
      (node (ref "MCU") (pin "22") (pinfunction "PD5_22") (pintype "bidirectional"))
      (node (ref "R24") (pin "2") (pinfunction "2_2") (pintype "passive"))
    )
    (net (code "40") (name "Net-(MCU-UCAP)") (class "Default")
      (node (ref "C12") (pin "2") (pinfunction "2_2") (pintype "passive"))
      (node (ref "MCU") (pin "6") (pinfunction "UCAP_6") (pintype "bidirectional"))
    )
    (net (code "41") (name "Net-(MCU-XTAL1)") (class "Default")
      (node (ref "C10") (pin "2") (pinfunction "2_2") (pintype "passive"))
      (node (ref "MCU") (pin "17") (pinfunction "XTAL1_17") (pintype "bidirectional"))
      (node (ref "Y1") (pin "3") (pinfunction "2_3") (pintype "passive"))
    )
    (net (code "42") (name "Net-(MCU-XTAL2)") (class "Default")
      (node (ref "C11") (pin "2") (pinfunction "2_2") (pintype "passive"))
      (node (ref "MCU") (pin "16") (pinfunction "XTAL2_16") (pintype "bidirectional"))
      (node (ref "Y1") (pin "1") (pinfunction "1_1") (pintype "passive"))
    )
    (net (code "43") (name "Net-(Q1-D)") (class "Default")
      (node (ref "Q1") (pin "3") (pinfunction "D_3") (pintype "passive"))
      (node (ref "Q3") (pin "2") (pinfunction "S_2") (pintype "passive"))
    )
    (net (code "44") (name "Net-(Q1-S)") (class "Default")
      (node (ref "D8") (pin "C") (pinfunction "C_C") (pintype "passive"))
      (node (ref "EXT_SW") (pin "1") (pinfunction "1_1") (pintype "passive"))
      (node (ref "Q1") (pin "2") (pinfunction "S_2") (pintype "passive"))
      (node (ref "S1") (pin "2") (pinfunction "P_2") (pintype "passive"))
    )
    (net (code "45") (name "Net-(Q2-D)") (class "Default")
      (node (ref "Q2") (pin "2") (pinfunction "D_2") (pintype "passive"))
      (node (ref "R30") (pin "1") (pinfunction "1_1") (pintype "passive"))
    )
    (net (code "46") (name "Net-(Q3-G)") (class "Default")
      (node (ref "Q3") (pin "1") (pinfunction "G_1") (pintype "passive"))
      (node (ref "U1") (pin "2") (pinfunction "RESET_2") (pintype "bidirectional"))
    )
    (net (code "47") (name "Net-(S1-O)") (class "Default")
      (node (ref "EXT_SW") (pin "2") (pinfunction "2_2") (pintype "passive"))
      (node (ref "S1") (pin "1") (pinfunction "O_1") (pintype "passive"))
      (node (ref "VREG") (pin "1") (pinfunction "IN_1") (pintype "power_in"))
    )
    (net (code "48") (name "Net-(XBEE-ASSOC{slash}AD5{slash}DIO5)") (class "Default")
      (node (ref "R26") (pin "2") (pinfunction "2_2") (pintype "passive"))
      (node (ref "XBEE") (pin "15") (pinfunction "ASSOC/AD5/DIO5_15") (pintype "bidirectional"))
    )
    (net (code "49") (name "Net-(XBEE-ON{slash}~{SLEEP})") (class "Default")
      (node (ref "R28") (pin "2") (pinfunction "2_2") (pintype "passive"))
      (node (ref "XBEE") (pin "13") (pinfunction "ON/~{SLEEP}_13") (pintype "output"))
    )
    (net (code "50") (name "Net-(XBEE-PWM0{slash}RSSI)") (class "Default")
      (node (ref "R27") (pin "2") (pinfunction "2_2") (pintype "passive"))
      (node (ref "XBEE") (pin "6") (pinfunction "PWM0/RSSI_6") (pintype "output"))
    )
    (net (code "51") (name "RST") (class "Default")
      (node (ref "ICSP") (pin "5") (pinfunction "5_5") (pintype "passive"))
      (node (ref "MCU") (pin "13") (pinfunction "~{RESET}_13") (pintype "bidirectional"))
      (node (ref "R23") (pin "2") (pinfunction "2_2") (pintype "passive"))
    )
    (net (code "52") (name "SCK") (class "Default")
      (node (ref "ICSP") (pin "3") (pinfunction "3_3") (pintype "passive"))
      (node (ref "MCU") (pin "9") (pinfunction "PB1(SCK)_9") (pintype "bidirectional"))
    )
    (net (code "53") (name "SCL_BM") (class "Default")
      (node (ref "BM") (pin "6") (pinfunction "SCL_6") (pintype "input"))
      (node (ref "MUX") (pin "20") (pinfunction "SC7_20") (pintype "bidirectional"))
      (node (ref "R22") (pin "1") (pinfunction "1_1") (pintype "passive"))
    )
    (net (code "54") (name "SDA_BM") (class "Default")
      (node (ref "BM") (pin "5") (pinfunction "SDA_5") (pintype "bidirectional"))
      (node (ref "MUX") (pin "19") (pinfunction "SD7_19") (pintype "bidirectional"))
      (node (ref "R21") (pin "1") (pinfunction "1_1") (pintype "passive"))
    )
    (net (code "55") (name "USB_5V0") (class "Default")
      (node (ref "CC") (pin "4") (pinfunction "VIN_4") (pintype "power_in"))
      (node (ref "D1") (pin "A") (pinfunction "A_A") (pintype "passive"))
      (node (ref "D2") (pin "A") (pinfunction "A_A") (pintype "passive"))
      (node (ref "D8") (pin "A") (pinfunction "A_A") (pintype "passive"))
      (node (ref "F1") (pin "2") (pinfunction "2_2") (pintype "bidirectional"))
      (node (ref "Q1") (pin "1") (pinfunction "G_1") (pintype "passive"))
      (node (ref "R29") (pin "2") (pinfunction "2_2") (pintype "passive"))
    )
    (net (code "56") (name "USB_5V0_UF") (class "Default")
      (node (ref "EXT_POWER") (pin "1") (pinfunction "1_1") (pintype "passive"))
      (node (ref "F1") (pin "1") (pinfunction "1_1") (pintype "bidirectional"))
      (node (ref "JP1") (pin "1") (pinfunction "VCC_1") (pintype "power_in"))
    )
    (net (code "57") (name "USB_N") (class "Default")
      (node (ref "MCU") (pin "3") (pinfunction "D-_3") (pintype "bidirectional"))
      (node (ref "R19") (pin "2") (pinfunction "2_2") (pintype "passive"))
    )
    (net (code "58") (name "USB_P") (class "Default")
      (node (ref "MCU") (pin "4") (pinfunction "D+_4") (pintype "bidirectional"))
      (node (ref "R20") (pin "2") (pinfunction "2_2") (pintype "passive"))
    )
    (net (code "59") (name "VCC_3V3") (class "Default")
      (node (ref "ACCEL") (pin "14") (pinfunction "VDD_14") (pintype "bidirectional"))
      (node (ref "BARO") (pin "10") (pinfunction "VDD_10") (pintype "power_in"))
      (node (ref "C1") (pin "1") (pinfunction "1_1") (pintype "passive"))
      (node (ref "C15") (pin "2") (pinfunction "2_2") (pintype "passive"))
      (node (ref "C17") (pin "+") (pinfunction "+_+") (pintype "passive"))
      (node (ref "C18") (pin "+") (pinfunction "+_+") (pintype "passive"))
      (node (ref "C19") (pin "+") (pinfunction "+_+") (pintype "passive"))
      (node (ref "C2") (pin "1") (pinfunction "1_1") (pintype "passive"))
      (node (ref "C3") (pin "1") (pinfunction "1_1") (pintype "passive"))
      (node (ref "C4") (pin "1") (pinfunction "1_1") (pintype "passive"))
      (node (ref "C5") (pin "1") (pinfunction "1_1") (pintype "passive"))
      (node (ref "C6") (pin "1") (pinfunction "1_1") (pintype "passive"))
      (node (ref "C7") (pin "+") (pinfunction "+_+") (pintype "passive"))
      (node (ref "C8") (pin "1") (pinfunction "1_1") (pintype "passive"))
      (node (ref "C9") (pin "1") (pinfunction "1_1") (pintype "passive"))
      (node (ref "D3") (pin "A") (pinfunction "A_A") (pintype "passive"))
      (node (ref "D4") (pin "A") (pinfunction "A_A") (pintype "passive"))
      (node (ref "DP0") (pin "P$2") (pinfunction "VS_P$2") (pintype "bidirectional"))
      (node (ref "DPA") (pin "P$2") (pinfunction "VS_P$2") (pintype "bidirectional"))
      (node (ref "DPB") (pin "P$2") (pinfunction "VS_P$2") (pintype "bidirectional"))
      (node (ref "EXT_OAT") (pin "1") (pinfunction "1_1") (pintype "passive"))
      (node (ref "ICSP") (pin "2") (pinfunction "2_2") (pintype "passive"))
      (node (ref "MCU") (pin "14") (pinfunction "VCC_14") (pintype "bidirectional"))
      (node (ref "MCU") (pin "24") (pinfunction "AVCC_24") (pintype "bidirectional"))
      (node (ref "MCU") (pin "34") (pinfunction "VCC_34") (pintype "bidirectional"))
      (node (ref "MCU") (pin "44") (pinfunction "AVCC_44") (pintype "bidirectional"))
      (node (ref "MUX") (pin "24") (pinfunction "VCC_24") (pintype "bidirectional"))
      (node (ref "R1") (pin "2") (pinfunction "2_2") (pintype "passive"))
      (node (ref "R10") (pin "2") (pinfunction "2_2") (pintype "passive"))
      (node (ref "R14") (pin "2") (pinfunction "2_2") (pintype "passive"))
      (node (ref "R16") (pin "2") (pinfunction "2_2") (pintype "passive"))
      (node (ref "R17") (pin "2") (pinfunction "2_2") (pintype "passive"))
      (node (ref "R2") (pin "2") (pinfunction "2_2") (pintype "passive"))
      (node (ref "R21") (pin "2") (pinfunction "2_2") (pintype "passive"))
      (node (ref "R22") (pin "2") (pinfunction "2_2") (pintype "passive"))
      (node (ref "R23") (pin "1") (pinfunction "1_1") (pintype "passive"))
      (node (ref "R3") (pin "2") (pinfunction "2_2") (pintype "passive"))
      (node (ref "R4") (pin "2") (pinfunction "2_2") (pintype "passive"))
      (node (ref "R5") (pin "2") (pinfunction "2_2") (pintype "passive"))
      (node (ref "R6") (pin "2") (pinfunction "2_2") (pintype "passive"))
      (node (ref "R7") (pin "2") (pinfunction "2_2") (pintype "passive"))
      (node (ref "R8") (pin "2") (pinfunction "2_2") (pintype "passive"))
      (node (ref "R9") (pin "2") (pinfunction "2_2") (pintype "passive"))
      (node (ref "VREG") (pin "3") (pinfunction "OUT_3") (pintype "power_in"))
      (node (ref "XBEE") (pin "1") (pinfunction "VCC_1") (pintype "power_in"))
    )
    (net (code "60") (name "VCC_5V0") (class "Default")
      (node (ref "C13") (pin "2") (pinfunction "2_2") (pintype "passive"))
      (node (ref "MCU") (pin "2") (pinfunction "UVCC_2") (pintype "bidirectional"))
      (node (ref "MCU") (pin "7") (pinfunction "VBUS_7") (pintype "bidirectional"))
    )
    (net (code "61") (name "VDDIO") (class "Default")
      (node (ref "BARO") (pin "1") (pinfunction "VDDIO_1") (pintype "power_in"))
    )
    (net (code "62") (name "unconnected-(ACCEL-ADC1-Pad16)") (class "Default")
      (node (ref "ACCEL") (pin "16") (pinfunction "ADC1_16") (pintype "bidirectional"))
    )
    (net (code "63") (name "unconnected-(ACCEL-ADC2-Pad15)") (class "Default")
      (node (ref "ACCEL") (pin "15") (pinfunction "ADC2_15") (pintype "bidirectional"))
    )
    (net (code "64") (name "unconnected-(ACCEL-ADC3-Pad13)") (class "Default")
      (node (ref "ACCEL") (pin "13") (pinfunction "ADC3_13") (pintype "bidirectional"))
    )
    (net (code "65") (name "unconnected-(ACCEL-GND-Pad12)") (class "Default")
      (node (ref "ACCEL") (pin "12") (pinfunction "GND_12") (pintype "bidirectional"))
    )
    (net (code "66") (name "unconnected-(ACCEL-INT1-Pad11)") (class "Default")
      (node (ref "ACCEL") (pin "11") (pinfunction "INT1_11") (pintype "bidirectional"))
    )
    (net (code "67") (name "unconnected-(ACCEL-INT2-Pad9)") (class "Default")
      (node (ref "ACCEL") (pin "9") (pinfunction "INT2_9") (pintype "bidirectional"))
    )
    (net (code "68") (name "unconnected-(ACCEL-RES-Pad10)") (class "Default")
      (node (ref "ACCEL") (pin "10") (pinfunction "RES_10") (pintype "bidirectional"))
    )
    (net (code "69") (name "unconnected-(ACCEL-SA0{slash}SDO-Pad7)") (class "Default")
      (node (ref "ACCEL") (pin "7") (pinfunction "SA0/SDO_7") (pintype "bidirectional"))
    )
    (net (code "70") (name "unconnected-(ACCEL-VDDIO-Pad1)") (class "Default")
      (node (ref "ACCEL") (pin "1") (pinfunction "VDDIO_1") (pintype "bidirectional"))
    )
    (net (code "71") (name "unconnected-(ACCEL-~{CS}{slash}MODE-Pad8)") (class "Default")
      (node (ref "ACCEL") (pin "8") (pinfunction "~{CS}/MODE_8") (pintype "bidirectional"))
    )
    (net (code "72") (name "unconnected-(BARO-CSB-Pad6)") (class "Default")
      (node (ref "BARO") (pin "6") (pinfunction "CSB_6") (pintype "input"))
    )
    (net (code "73") (name "unconnected-(BARO-INT-Pad7)") (class "Default")
      (node (ref "BARO") (pin "7") (pinfunction "INT_7") (pintype "output"))
    )
    (net (code "74") (name "unconnected-(BARO-SDO-Pad5)") (class "Default")
      (node (ref "BARO") (pin "5") (pinfunction "SDO_5") (pintype "bidirectional"))
    )
    (net (code "75") (name "unconnected-(BM-PIO-Pad8)") (class "Default")
      (node (ref "BM") (pin "8") (pinfunction "PIO_8") (pintype "bidirectional"))
    )
    (net (code "76") (name "unconnected-(J1-PAD1-PadNC1)") (class "Default")
      (node (ref "J1") (pin "NC1") (pinfunction "PAD1_NC1") (pintype "bidirectional"))
    )
    (net (code "77") (name "unconnected-(J1-PAD2-PadNC2)") (class "Default")
      (node (ref "J1") (pin "NC2") (pinfunction "PAD2_NC2") (pintype "bidirectional"))
    )
    (net (code "78") (name "unconnected-(JP1-ID-Pad4)") (class "Default")
      (node (ref "JP1") (pin "4") (pinfunction "ID_4") (pintype "bidirectional"))
    )
    (net (code "79") (name "unconnected-(MCU-PB4(ADC11)-Pad28)") (class "Default")
      (node (ref "MCU") (pin "28") (pinfunction "PB4(ADC11)_28") (pintype "bidirectional"))
    )
    (net (code "80") (name "unconnected-(MCU-PB5(ADC12)-Pad29)") (class "Default")
      (node (ref "MCU") (pin "29") (pinfunction "PB5(ADC12)_29") (pintype "bidirectional"))
    )
    (net (code "81") (name "unconnected-(MCU-PB6(ADC13)-Pad30)") (class "Default")
      (node (ref "MCU") (pin "30") (pinfunction "PB6(ADC13)_30") (pintype "bidirectional"))
    )
    (net (code "82") (name "unconnected-(MCU-PB7-Pad12)") (class "Default")
      (node (ref "MCU") (pin "12") (pinfunction "PB7_12") (pintype "bidirectional"))
    )
    (net (code "83") (name "unconnected-(MCU-PC6-Pad31)") (class "Default")
      (node (ref "MCU") (pin "31") (pinfunction "PC6_31") (pintype "bidirectional"))
    )
    (net (code "84") (name "unconnected-(MCU-PD6(ADC9)-Pad26)") (class "Default")
      (node (ref "MCU") (pin "26") (pinfunction "PD6(ADC9)_26") (pintype "bidirectional"))
    )
    (net (code "85") (name "unconnected-(MCU-PD7(ADC10)-Pad27)") (class "Default")
      (node (ref "MCU") (pin "27") (pinfunction "PD7(ADC10)_27") (pintype "bidirectional"))
    )
    (net (code "86") (name "unconnected-(MCU-PE6-Pad1)") (class "Default")
      (node (ref "MCU") (pin "1") (pinfunction "PE6_1") (pintype "bidirectional"))
    )
    (net (code "87") (name "unconnected-(MCU-PF1(ADC1)-Pad40)") (class "Default")
      (node (ref "MCU") (pin "40") (pinfunction "PF1(ADC1)_40") (pintype "bidirectional"))
    )
    (net (code "88") (name "unconnected-(MCU-PF4(ADC4)-Pad39)") (class "Default")
      (node (ref "MCU") (pin "39") (pinfunction "PF4(ADC4)_39") (pintype "bidirectional"))
    )
    (net (code "89") (name "unconnected-(MCU-PF5(ADC5)-Pad38)") (class "Default")
      (node (ref "MCU") (pin "38") (pinfunction "PF5(ADC5)_38") (pintype "bidirectional"))
    )
    (net (code "90") (name "unconnected-(MCU-PF6(ADC6)-Pad37)") (class "Default")
      (node (ref "MCU") (pin "37") (pinfunction "PF6(ADC6)_37") (pintype "bidirectional"))
    )
    (net (code "91") (name "unconnected-(MCU-PF7(ADC7)-Pad36)") (class "Default")
      (node (ref "MCU") (pin "36") (pinfunction "PF7(ADC7)_36") (pintype "bidirectional"))
    )
    (net (code "92") (name "unconnected-(MUX-SC5-Pad16)") (class "Default")
      (node (ref "MUX") (pin "16") (pinfunction "SC5_16") (pintype "bidirectional"))
    )
    (net (code "93") (name "unconnected-(MUX-SC6-Pad18)") (class "Default")
      (node (ref "MUX") (pin "18") (pinfunction "SC6_18") (pintype "bidirectional"))
    )
    (net (code "94") (name "unconnected-(MUX-SD5-Pad15)") (class "Default")
      (node (ref "MUX") (pin "15") (pinfunction "SD5_15") (pintype "bidirectional"))
    )
    (net (code "95") (name "unconnected-(MUX-SD6-Pad17)") (class "Default")
      (node (ref "MUX") (pin "17") (pinfunction "SD6_17") (pintype "bidirectional"))
    )
    (net (code "96") (name "unconnected-(S1-S-Pad3)") (class "Default")
      (node (ref "S1") (pin "3") (pinfunction "S_3") (pintype "passive"))
    )
    (net (code "97") (name "unconnected-(XBEE-AD0{slash}DIO0-Pad20)") (class "Default")
      (node (ref "XBEE") (pin "20") (pinfunction "AD0/DIO0_20") (pintype "bidirectional"))
    )
    (net (code "98") (name "unconnected-(XBEE-AD1{slash}DIO1-Pad19)") (class "Default")
      (node (ref "XBEE") (pin "19") (pinfunction "AD1/DIO1_19") (pintype "bidirectional"))
    )
    (net (code "99") (name "unconnected-(XBEE-AD2{slash}DIO2-Pad18)") (class "Default")
      (node (ref "XBEE") (pin "18") (pinfunction "AD2/DIO2_18") (pintype "bidirectional"))
    )
    (net (code "100") (name "unconnected-(XBEE-CD{slash}DOUT_EN{slash}DO8-Pad4)") (class "Default")
      (node (ref "XBEE") (pin "4") (pinfunction "CD/DOUT_EN/DO8_4") (pintype "output"))
    )
    (net (code "101") (name "unconnected-(XBEE-COORD_SEL{slash}AD3{slash}DIO3-Pad17)") (class "Default")
      (node (ref "XBEE") (pin "17") (pinfunction "COORD_SEL/AD3/DIO3_17") (pintype "bidirectional"))
    )
    (net (code "102") (name "unconnected-(XBEE-RF_TX{slash}AD4{slash}DIO4-Pad11)") (class "Default")
      (node (ref "XBEE") (pin "11") (pinfunction "RF_TX/AD4/DIO4_11") (pintype "bidirectional"))
    )
    (net (code "103") (name "unconnected-(XBEE-VREF-Pad14)") (class "Default")
      (node (ref "XBEE") (pin "14") (pinfunction "VREF_14") (pintype "input"))
    )
    (net (code "104") (name "unconnected-(XBEE-~{CTS}{slash}DIO7-Pad12)") (class "Default")
      (node (ref "XBEE") (pin "12") (pinfunction "~{CTS}/DIO7_12") (pintype "bidirectional"))
    )
    (net (code "105") (name "unconnected-(XBEE-~{RESET}-Pad5)") (class "Default")
      (node (ref "XBEE") (pin "5") (pinfunction "~{RESET}_5") (pintype "input"))
    )
    (net (code "106") (name "unconnected-(XBEE-~{RTS}{slash}AD6{slash}DIO6-Pad16)") (class "Default")
      (node (ref "XBEE") (pin "16") (pinfunction "~{RTS}/AD6/DIO6_16") (pintype "bidirectional"))
    )
  )
)
